# HardwareSetup.net
KiCad netlist of a schematic drawn in Altium Designer
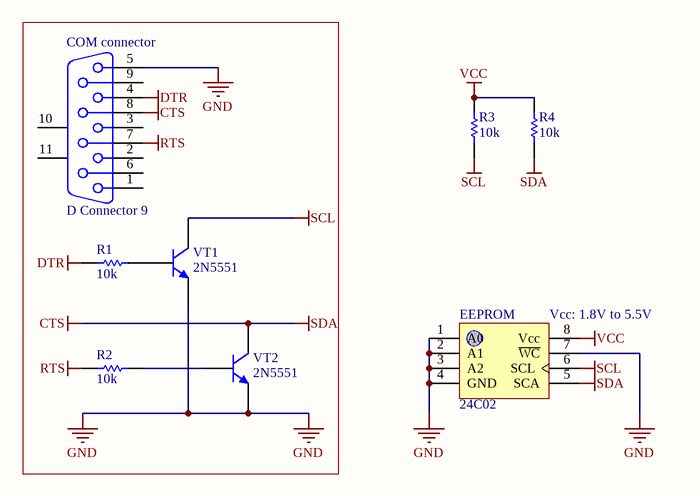
[diagram p0: HardwareSetup.SchDoc]

(export (version "E")
  (design (tool "Eeschema 10.0.6"))
  (components
    (comp (ref "COM connector")
      (value "D Connector 9")
      (footprint "DSUB1.385-2H9")
      (description "Receptacle Assembly, 9 Position, Right Angle")
      (fields (field (name "PUBLISHER") "Altium Limited"))
      (libsource (lib "Miscellaneous Connectors") (part "D Connector 9"))
    )
    (comp (ref "EEPROM")
      (value "24C02")
      (footprint "DIP-8")
      (libsource (lib "MicroControllers") (part "24C02"))
    )
    (comp (ref "R1")
      (value "10k")
      (footprint "AXIAL-0.3")
      (description "Resistor")
      (fields (field (name "Comment") "R1") (field (name "PUBLISHER") "Altium Limited"))
      (libsource (lib "Miscellaneous Devices") (part "Res1"))
    )
    (comp (ref "R2")
      (value "10k")
      (footprint "AXIAL-0.3")
      (description "Resistor")
      (fields (field (name "Comment") "R1") (field (name "PUBLISHER") "Altium Limited"))
      (libsource (lib "Miscellaneous Devices") (part "Res1"))
    )
    (comp (ref "R3")
      (value "10k")
      (footprint "AXIAL-0.3")
      (description "Resistor")
      (fields (field (name "Comment") "R1") (field (name "PUBLISHER") "Altium Limited"))
      (libsource (lib "Miscellaneous Devices") (part "Res1"))
    )
    (comp (ref "R4")
      (value "10k")
      (footprint "AXIAL-0.3")
      (description "Resistor")
      (fields (field (name "Comment") "R1") (field (name "PUBLISHER") "Altium Limited"))
      (libsource (lib "Miscellaneous Devices") (part "Res1"))
    )
    (comp (ref "VT1")
      (value "2N5551")
      (footprint "TO-92B")
      (libsource (lib "Basic Components") (part "NPN_2N5551"))
    )
    (comp (ref "VT2")
      (value "2N5551")
      (footprint "TO-92B")
      (libsource (lib "Basic Components") (part "NPN_2N5551"))
    )
  )
  (nets
    (net (code "1") (name "CTS") (class "Default")
      (node (ref "COM connector") (pin "8") (pinfunction "8_8") (pintype "passive"))
      (node (ref "EEPROM") (pin "5") (pinfunction "SCA_5") (pintype "passive"))
      (node (ref "R4") (pin "1") (pinfunction "1_1") (pintype "passive"))
      (node (ref "VT2") (pin "3") (pinfunction "C_3") (pintype "passive"))
    )
    (net (code "2") (name "DTR") (class "Default")
      (node (ref "COM connector") (pin "4") (pinfunction "4_4") (pintype "passive"))
      (node (ref "R1") (pin "1") (pinfunction "1_1") (pintype "passive"))
    )
    (net (code "3") (name "GND") (class "Default")
      (node (ref "COM connector") (pin "5") (pinfunction "5_5") (pintype "passive"))
      (node (ref "EEPROM") (pin "1") (pinfunction "A0_1") (pintype "passive"))
      (node (ref "EEPROM") (pin "2") (pinfunction "A1_2") (pintype "passive"))
      (node (ref "EEPROM") (pin "3") (pinfunction "A2_3") (pintype "passive"))
      (node (ref "EEPROM") (pin "4") (pinfunction "GND_4") (pintype "passive"))
      (node (ref "EEPROM") (pin "7") (pinfunction "~{WC}_7") (pintype "passive"))
      (node (ref "VT1") (pin "1") (pinfunction "E_1") (pintype "passive"))
      (node (ref "VT2") (pin "1") (pinfunction "E_1") (pintype "passive"))
    )
    (net (code "4") (name "Net-(VT1-B)") (class "Default")
      (node (ref "R1") (pin "2") (pinfunction "2_2") (pintype "passive"))
      (node (ref "VT1") (pin "2") (pinfunction "B_2") (pintype "passive"))
    )
    (net (code "5") (name "Net-(VT2-B)") (class "Default")
      (node (ref "R2") (pin "2") (pinfunction "2_2") (pintype "passive"))
      (node (ref "VT2") (pin "2") (pinfunction "B_2") (pintype "passive"))
    )
    (net (code "6") (name "RTS") (class "Default")
      (node (ref "COM connector") (pin "7") (pinfunction "7_7") (pintype "passive"))
      (node (ref "R2") (pin "1") (pinfunction "1_1") (pintype "passive"))
    )
    (net (code "7") (name "SCL") (class "Default")
      (node (ref "EEPROM") (pin "6") (pinfunction "SCL_6") (pintype "passive"))
      (node (ref "R3") (pin "1") (pinfunction "1_1") (pintype "passive"))
      (node (ref "VT1") (pin "3") (pinfunction "C_3") (pintype "passive"))
    )
    (net (code "8") (name "VCC") (class "Default")
      (node (ref "EEPROM") (pin "8") (pinfunction "Vcc_8") (pintype "passive"))
      (node (ref "R3") (pin "2") (pinfunction "2_2") (pintype "passive"))
      (node (ref "R4") (pin "2") (pinfunction "2_2") (pintype "passive"))
    )
    (net (code "9") (name "unconnected-(COM connector-MH1-Pad10)") (class "Default")
      (node (ref "COM connector") (pin "10") (pinfunction "MH1_10") (pintype "passive"))
    )
    (net (code "10") (name "unconnected-(COM connector-MH2-Pad11)") (class "Default")
      (node (ref "COM connector") (pin "11") (pinfunction "MH2_11") (pintype "passive"))
    )
    (net (code "11") (name "unconnected-(COM connector-Pad1)") (class "Default")
      (node (ref "COM connector") (pin "1") (pinfunction "1_1") (pintype "passive"))
    )
    (net (code "12") (name "unconnected-(COM connector-Pad2)") (class "Default")
      (node (ref "COM connector") (pin "2") (pinfunction "2_2") (pintype "passive"))
    )
    (net (code "13") (name "unconnected-(COM connector-Pad3)") (class "Default")
      (node (ref "COM connector") (pin "3") (pinfunction "3_3") (pintype "passive"))
    )
    (net (code "14") (name "unconnected-(COM connector-Pad6)") (class "Default")
      (node (ref "COM connector") (pin "6") (pinfunction "6_6") (pintype "passive"))
    )
    (net (code "15") (name "unconnected-(COM connector-Pad9)") (class "Default")
      (node (ref "COM connector") (pin "9") (pinfunction "9_9") (pintype "passive"))
    )
  )
)
